# Spannungsversorgung_V1.net
KiCad netlist of a schematic drawn in EAGLE
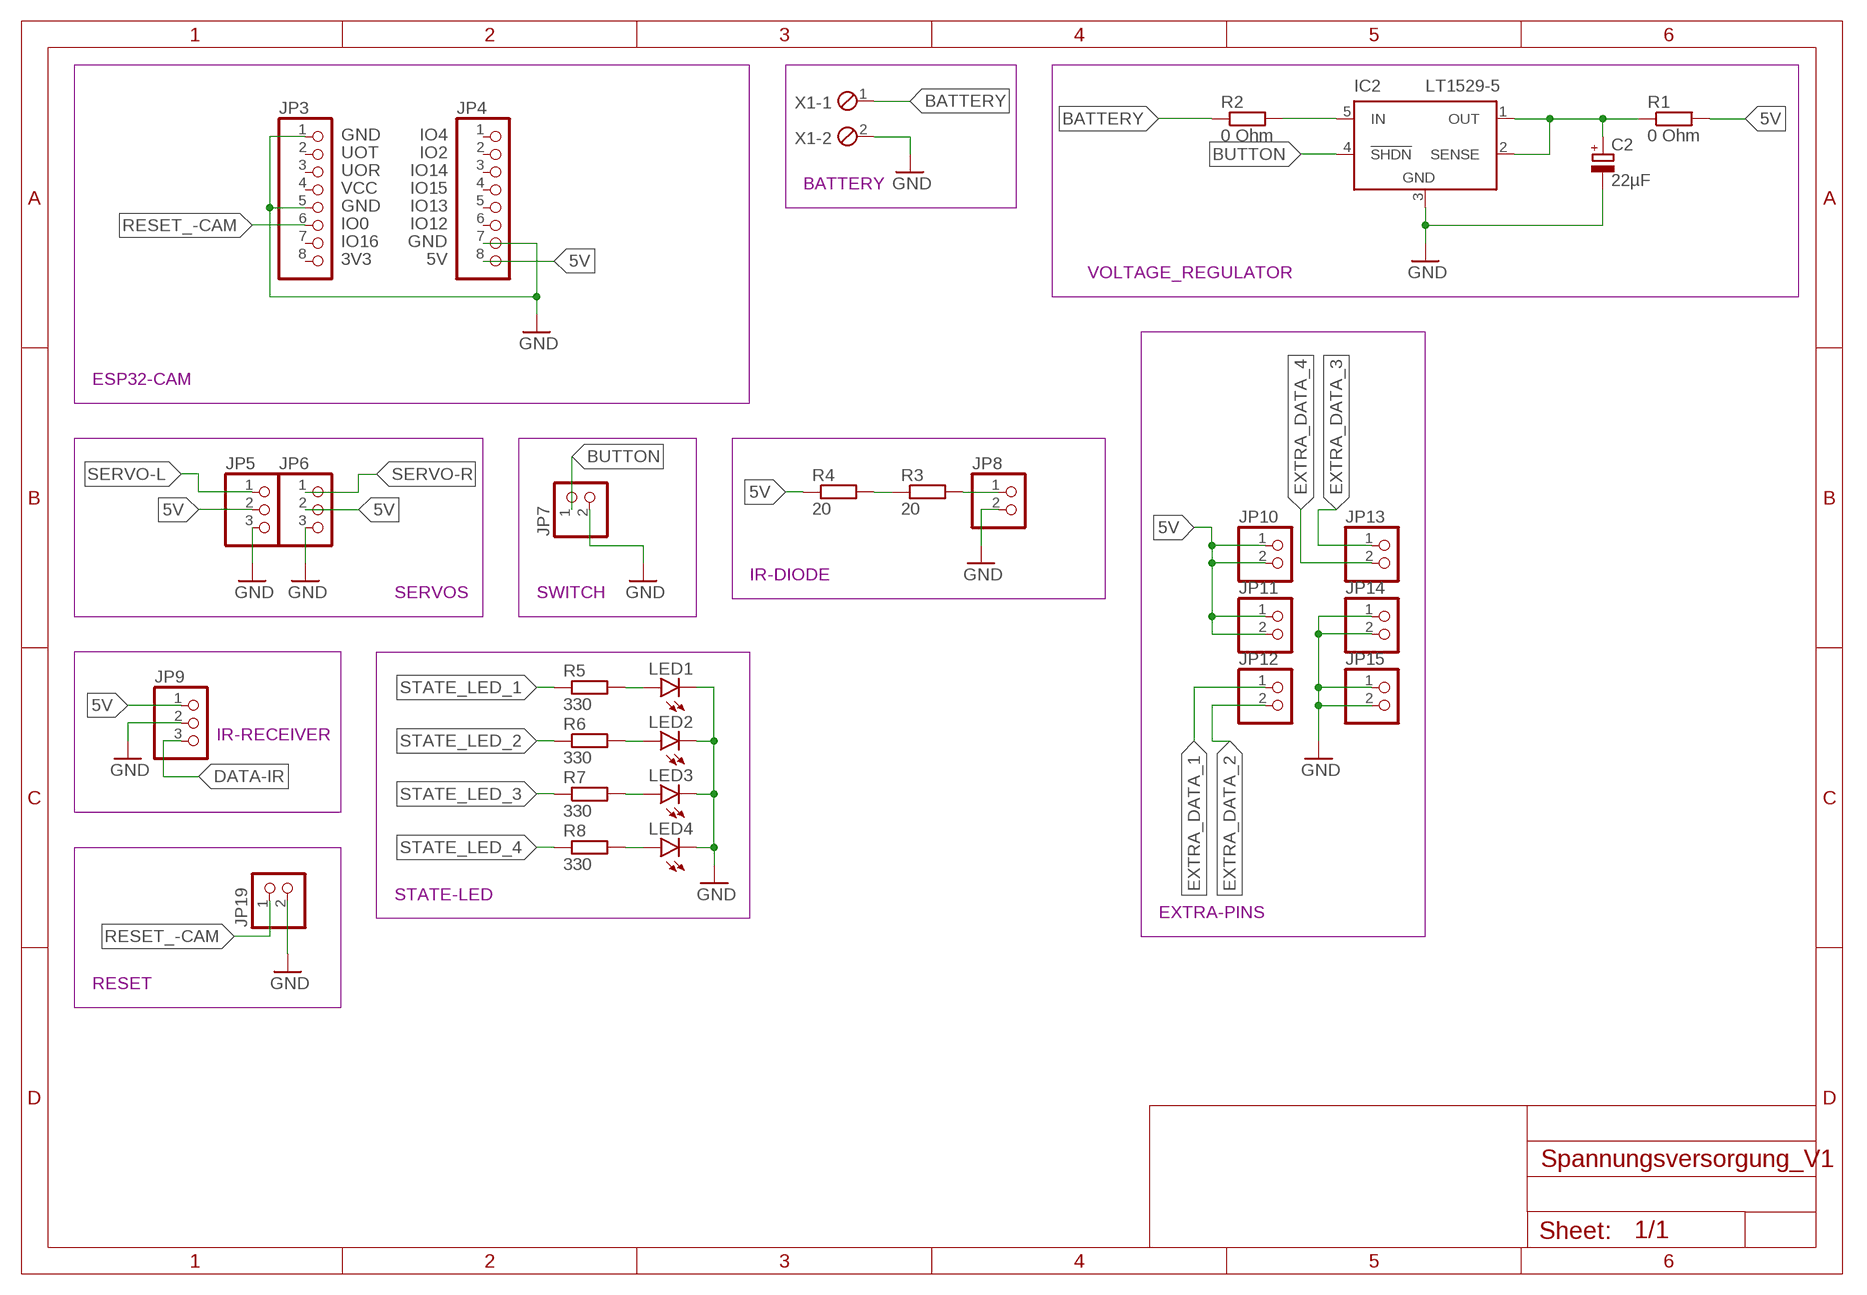
[diagram p0: schematic, sheet 1]

(export (version "E")
  (design (tool "Eeschema 10.0.6"))
  (components
    (comp (ref "C2")
      (value "22µF")
      (footprint "eagle-import:E2,5-5")
      (libsource (lib "eagle-import") (part "CPOL-EUE2.5-5"))
    )
    (comp (ref "IC2")
      (value "LT1529-5")
      (footprint "eagle-import:TO220-5")
      (libsource (lib "eagle-import") (part "LT1529T"))
    )
    (comp (ref "JP3")
      (value "PINHD-1X8")
      (footprint "eagle-import:1X08")
      (libsource (lib "eagle-import") (part "PINHD-1X8"))
    )
    (comp (ref "JP4")
      (value "PINHD-1X8")
      (footprint "eagle-import:1X08")
      (libsource (lib "eagle-import") (part "PINHD-1X8"))
    )
    (comp (ref "JP5")
      (value "PINHD-1X3")
      (footprint "eagle-import:1X03")
      (libsource (lib "eagle-import") (part "PINHD-1X3"))
    )
    (comp (ref "JP6")
      (value "PINHD-1X3")
      (footprint "eagle-import:1X03")
      (libsource (lib "eagle-import") (part "PINHD-1X3"))
    )
    (comp (ref "JP7")
      (value "PINHD-1X2")
      (footprint "eagle-import:1X02")
      (libsource (lib "eagle-import") (part "PINHD-1X2"))
    )
    (comp (ref "JP8")
      (value "PINHD-1X2")
      (footprint "eagle-import:1X02")
      (libsource (lib "eagle-import") (part "PINHD-1X2"))
    )
    (comp (ref "JP9")
      (value "PINHD-1X3")
      (footprint "eagle-import:1X03")
      (libsource (lib "eagle-import") (part "PINHD-1X3"))
    )
    (comp (ref "JP10")
      (value "PINHD-1X2")
      (footprint "eagle-import:1X02")
      (libsource (lib "eagle-import") (part "PINHD-1X2"))
    )
    (comp (ref "JP11")
      (value "PINHD-1X2")
      (footprint "eagle-import:1X02")
      (libsource (lib "eagle-import") (part "PINHD-1X2"))
    )
    (comp (ref "JP12")
      (value "PINHD-1X2")
      (footprint "eagle-import:1X02")
      (libsource (lib "eagle-import") (part "PINHD-1X2"))
    )
    (comp (ref "JP13")
      (value "PINHD-1X2")
      (footprint "eagle-import:1X02")
      (libsource (lib "eagle-import") (part "PINHD-1X2"))
    )
    (comp (ref "JP14")
      (value "PINHD-1X2")
      (footprint "eagle-import:1X02")
      (libsource (lib "eagle-import") (part "PINHD-1X2"))
    )
    (comp (ref "JP15")
      (value "PINHD-1X2")
      (footprint "eagle-import:1X02")
      (libsource (lib "eagle-import") (part "PINHD-1X2"))
    )
    (comp (ref "JP19")
      (value "PINHD-1X2")
      (footprint "eagle-import:1X02")
      (libsource (lib "eagle-import") (part "PINHD-1X2"))
    )
    (comp (ref "LED1")
      (value "LED3MM")
      (footprint "eagle-import:LED3MM")
      (libsource (lib "eagle-import") (part "LED3MM"))
    )
    (comp (ref "LED2")
      (value "LED3MM")
      (footprint "eagle-import:LED3MM")
      (libsource (lib "eagle-import") (part "LED3MM"))
    )
    (comp (ref "LED3")
      (value "LED3MM")
      (footprint "eagle-import:LED3MM")
      (libsource (lib "eagle-import") (part "LED3MM"))
    )
    (comp (ref "LED4")
      (value "LED3MM")
      (footprint "eagle-import:LED3MM")
      (libsource (lib "eagle-import") (part "LED3MM"))
    )
    (comp (ref "R1")
      (value "0 Ohm")
      (footprint "eagle-import:R0805")
      (libsource (lib "eagle-import") (part "R-EU_R0805"))
    )
    (comp (ref "R2")
      (value "0 Ohm")
      (footprint "eagle-import:R0805")
      (libsource (lib "eagle-import") (part "R-EU_R0805"))
    )
    (comp (ref "R3")
      (value "20")
      (footprint "eagle-import:0309_12")
      (libsource (lib "eagle-import") (part "R-EU_0309/12"))
    )
    (comp (ref "R4")
      (value "20")
      (footprint "eagle-import:0309_12")
      (libsource (lib "eagle-import") (part "R-EU_0309/12"))
    )
    (comp (ref "R5")
      (value "330")
      (footprint "eagle-import:R0805")
      (libsource (lib "eagle-import") (part "R-EU_R0805"))
    )
    (comp (ref "R6")
      (value "330")
      (footprint "eagle-import:R0805")
      (libsource (lib "eagle-import") (part "R-EU_R0805"))
    )
    (comp (ref "R7")
      (value "330")
      (footprint "eagle-import:R0805")
      (libsource (lib "eagle-import") (part "R-EU_R0805"))
    )
    (comp (ref "R8")
      (value "330")
      (footprint "eagle-import:R0805")
      (libsource (lib "eagle-import") (part "R-EU_R0805"))
    )
    (comp (ref "X1")
      (value "MPT2")
      (footprint "eagle-import:2POL254")
      (libsource (lib "eagle-import") (part "MPT2"))
    )
  )
  (nets
    (net (code "1") (name "5V") (class "Default")
      (node (ref "JP10") (pin "1") (pinfunction "1_1") (pintype "passive"))
      (node (ref "JP10") (pin "2") (pinfunction "2_2") (pintype "passive"))
      (node (ref "JP11") (pin "1") (pinfunction "1_1") (pintype "passive"))
      (node (ref "JP11") (pin "2") (pinfunction "2_2") (pintype "passive"))
      (node (ref "JP4") (pin "8") (pinfunction "8_8") (pintype "passive"))
      (node (ref "JP5") (pin "2") (pinfunction "2_2") (pintype "passive"))
      (node (ref "JP6") (pin "2") (pinfunction "2_2") (pintype "passive"))
      (node (ref "JP9") (pin "1") (pinfunction "1_1") (pintype "passive"))
      (node (ref "R1") (pin "2") (pinfunction "2_2") (pintype "passive"))
      (node (ref "R4") (pin "1") (pinfunction "1_1") (pintype "passive"))
    )
    (net (code "2") (name "BATTERY") (class "Default")
      (node (ref "R2") (pin "1") (pinfunction "1_1") (pintype "passive"))
      (node (ref "X1") (pin "1") (pinfunction "1_1") (pintype "passive"))
    )
    (net (code "3") (name "BUTTON") (class "Default")
      (node (ref "IC2") (pin "4") (pinfunction "~{SHDN}_4") (pintype "input"))
      (node (ref "JP7") (pin "1") (pinfunction "1_1") (pintype "passive"))
    )
    (net (code "4") (name "DATA-IR") (class "Default")
      (node (ref "JP9") (pin "3") (pinfunction "3_3") (pintype "passive"))
    )
    (net (code "5") (name "EXTRA_DATA_1") (class "Default")
      (node (ref "JP12") (pin "1") (pinfunction "1_1") (pintype "passive"))
    )
    (net (code "6") (name "EXTRA_DATA_2") (class "Default")
      (node (ref "JP12") (pin "2") (pinfunction "2_2") (pintype "passive"))
    )
    (net (code "7") (name "EXTRA_DATA_3") (class "Default")
      (node (ref "JP13") (pin "1") (pinfunction "1_1") (pintype "passive"))
    )
    (net (code "8") (name "EXTRA_DATA_4") (class "Default")
      (node (ref "JP13") (pin "2") (pinfunction "2_2") (pintype "passive"))
    )
    (net (code "9") (name "GND") (class "Default")
      (node (ref "C2") (pin "-") (pinfunction "-_-") (pintype "passive"))
      (node (ref "IC2") (pin "3") (pinfunction "GND_3") (pintype "power_in"))
      (node (ref "JP14") (pin "1") (pinfunction "1_1") (pintype "passive"))
      (node (ref "JP14") (pin "2") (pinfunction "2_2") (pintype "passive"))
      (node (ref "JP15") (pin "1") (pinfunction "1_1") (pintype "passive"))
      (node (ref "JP15") (pin "2") (pinfunction "2_2") (pintype "passive"))
      (node (ref "JP19") (pin "2") (pinfunction "2_2") (pintype "passive"))
      (node (ref "JP3") (pin "1") (pinfunction "1_1") (pintype "passive"))
      (node (ref "JP3") (pin "5") (pinfunction "5_5") (pintype "passive"))
      (node (ref "JP4") (pin "7") (pinfunction "7_7") (pintype "passive"))
      (node (ref "JP5") (pin "3") (pinfunction "3_3") (pintype "passive"))
      (node (ref "JP6") (pin "3") (pinfunction "3_3") (pintype "passive"))
      (node (ref "JP7") (pin "2") (pinfunction "2_2") (pintype "passive"))
      (node (ref "JP8") (pin "2") (pinfunction "2_2") (pintype "passive"))
      (node (ref "JP9") (pin "2") (pinfunction "2_2") (pintype "passive"))
      (node (ref "LED1") (pin "K") (pinfunction "C_K") (pintype "passive"))
      (node (ref "LED2") (pin "K") (pinfunction "C_K") (pintype "passive"))
      (node (ref "LED3") (pin "K") (pinfunction "C_K") (pintype "passive"))
      (node (ref "LED4") (pin "K") (pinfunction "C_K") (pintype "passive"))
      (node (ref "X1") (pin "2") (pinfunction "1_2") (pintype "passive"))
    )
    (net (code "10") (name "Net-(IC2-IN)") (class "Default")
      (node (ref "IC2") (pin "5") (pinfunction "IN_5") (pintype "input"))
      (node (ref "R2") (pin "2") (pinfunction "2_2") (pintype "passive"))
    )
    (net (code "11") (name "Net-(IC2-OUT)") (class "Default")
      (node (ref "C2") (pin "+") (pinfunction "+_+") (pintype "passive"))
      (node (ref "IC2") (pin "1") (pinfunction "OUT_1") (pintype "output"))
      (node (ref "IC2") (pin "2") (pinfunction "SENSE_2") (pintype "input"))
      (node (ref "R1") (pin "1") (pinfunction "1_1") (pintype "passive"))
    )
    (net (code "12") (name "Net-(JP8-Pad1)") (class "Default")
      (node (ref "JP8") (pin "1") (pinfunction "1_1") (pintype "passive"))
      (node (ref "R3") (pin "2") (pinfunction "2_2") (pintype "passive"))
    )
    (net (code "13") (name "Net-(LED1-PadA)") (class "Default")
      (node (ref "LED1") (pin "A") (pinfunction "A_A") (pintype "passive"))
      (node (ref "R5") (pin "2") (pinfunction "2_2") (pintype "passive"))
    )
    (net (code "14") (name "Net-(LED2-PadA)") (class "Default")
      (node (ref "LED2") (pin "A") (pinfunction "A_A") (pintype "passive"))
      (node (ref "R6") (pin "2") (pinfunction "2_2") (pintype "passive"))
    )
    (net (code "15") (name "Net-(LED3-PadA)") (class "Default")
      (node (ref "LED3") (pin "A") (pinfunction "A_A") (pintype "passive"))
      (node (ref "R7") (pin "2") (pinfunction "2_2") (pintype "passive"))
    )
    (net (code "16") (name "Net-(LED4-PadA)") (class "Default")
      (node (ref "LED4") (pin "A") (pinfunction "A_A") (pintype "passive"))
      (node (ref "R8") (pin "2") (pinfunction "2_2") (pintype "passive"))
    )
    (net (code "17") (name "Net-(R3-Pad1)") (class "Default")
      (node (ref "R3") (pin "1") (pinfunction "1_1") (pintype "passive"))
      (node (ref "R4") (pin "2") (pinfunction "2_2") (pintype "passive"))
    )
    (net (code "18") (name "RESET_-CAM") (class "Default")
      (node (ref "JP19") (pin "1") (pinfunction "1_1") (pintype "passive"))
      (node (ref "JP3") (pin "6") (pinfunction "6_6") (pintype "passive"))
    )
    (net (code "19") (name "SERVO-L") (class "Default")
      (node (ref "JP5") (pin "1") (pinfunction "1_1") (pintype "passive"))
    )
    (net (code "20") (name "SERVO-R") (class "Default")
      (node (ref "JP6") (pin "1") (pinfunction "1_1") (pintype "passive"))
    )
    (net (code "21") (name "STATE_LED_1") (class "Default")
      (node (ref "R5") (pin "1") (pinfunction "1_1") (pintype "passive"))
    )
    (net (code "22") (name "STATE_LED_2") (class "Default")
      (node (ref "R6") (pin "1") (pinfunction "1_1") (pintype "passive"))
    )
    (net (code "23") (name "STATE_LED_3") (class "Default")
      (node (ref "R7") (pin "1") (pinfunction "1_1") (pintype "passive"))
    )
    (net (code "24") (name "STATE_LED_4") (class "Default")
      (node (ref "R8") (pin "1") (pinfunction "1_1") (pintype "passive"))
    )
    (net (code "25") (name "unconnected-(JP3-Pad2)") (class "Default")
      (node (ref "JP3") (pin "2") (pinfunction "2_2") (pintype "passive"))
    )
    (net (code "26") (name "unconnected-(JP3-Pad3)") (class "Default")
      (node (ref "JP3") (pin "3") (pinfunction "3_3") (pintype "passive"))
    )
    (net (code "27") (name "unconnected-(JP3-Pad4)") (class "Default")
      (node (ref "JP3") (pin "4") (pinfunction "4_4") (pintype "passive"))
    )
    (net (code "28") (name "unconnected-(JP3-Pad7)") (class "Default")
      (node (ref "JP3") (pin "7") (pinfunction "7_7") (pintype "passive"))
    )
    (net (code "29") (name "unconnected-(JP3-Pad8)") (class "Default")
      (node (ref "JP3") (pin "8") (pinfunction "8_8") (pintype "passive"))
    )
    (net (code "30") (name "unconnected-(JP4-Pad1)") (class "Default")
      (node (ref "JP4") (pin "1") (pinfunction "1_1") (pintype "passive"))
    )
    (net (code "31") (name "unconnected-(JP4-Pad2)") (class "Default")
      (node (ref "JP4") (pin "2") (pinfunction "2_2") (pintype "passive"))
    )
    (net (code "32") (name "unconnected-(JP4-Pad3)") (class "Default")
      (node (ref "JP4") (pin "3") (pinfunction "3_3") (pintype "passive"))
    )
    (net (code "33") (name "unconnected-(JP4-Pad4)") (class "Default")
      (node (ref "JP4") (pin "4") (pinfunction "4_4") (pintype "passive"))
    )
    (net (code "34") (name "unconnected-(JP4-Pad5)") (class "Default")
      (node (ref "JP4") (pin "5") (pinfunction "5_5") (pintype "passive"))
    )
    (net (code "35") (name "unconnected-(JP4-Pad6)") (class "Default")
      (node (ref "JP4") (pin "6") (pinfunction "6_6") (pintype "passive"))
    )
  )
)
